# compressor.net
KiCad netlist of a schematic drawn in EAGLE
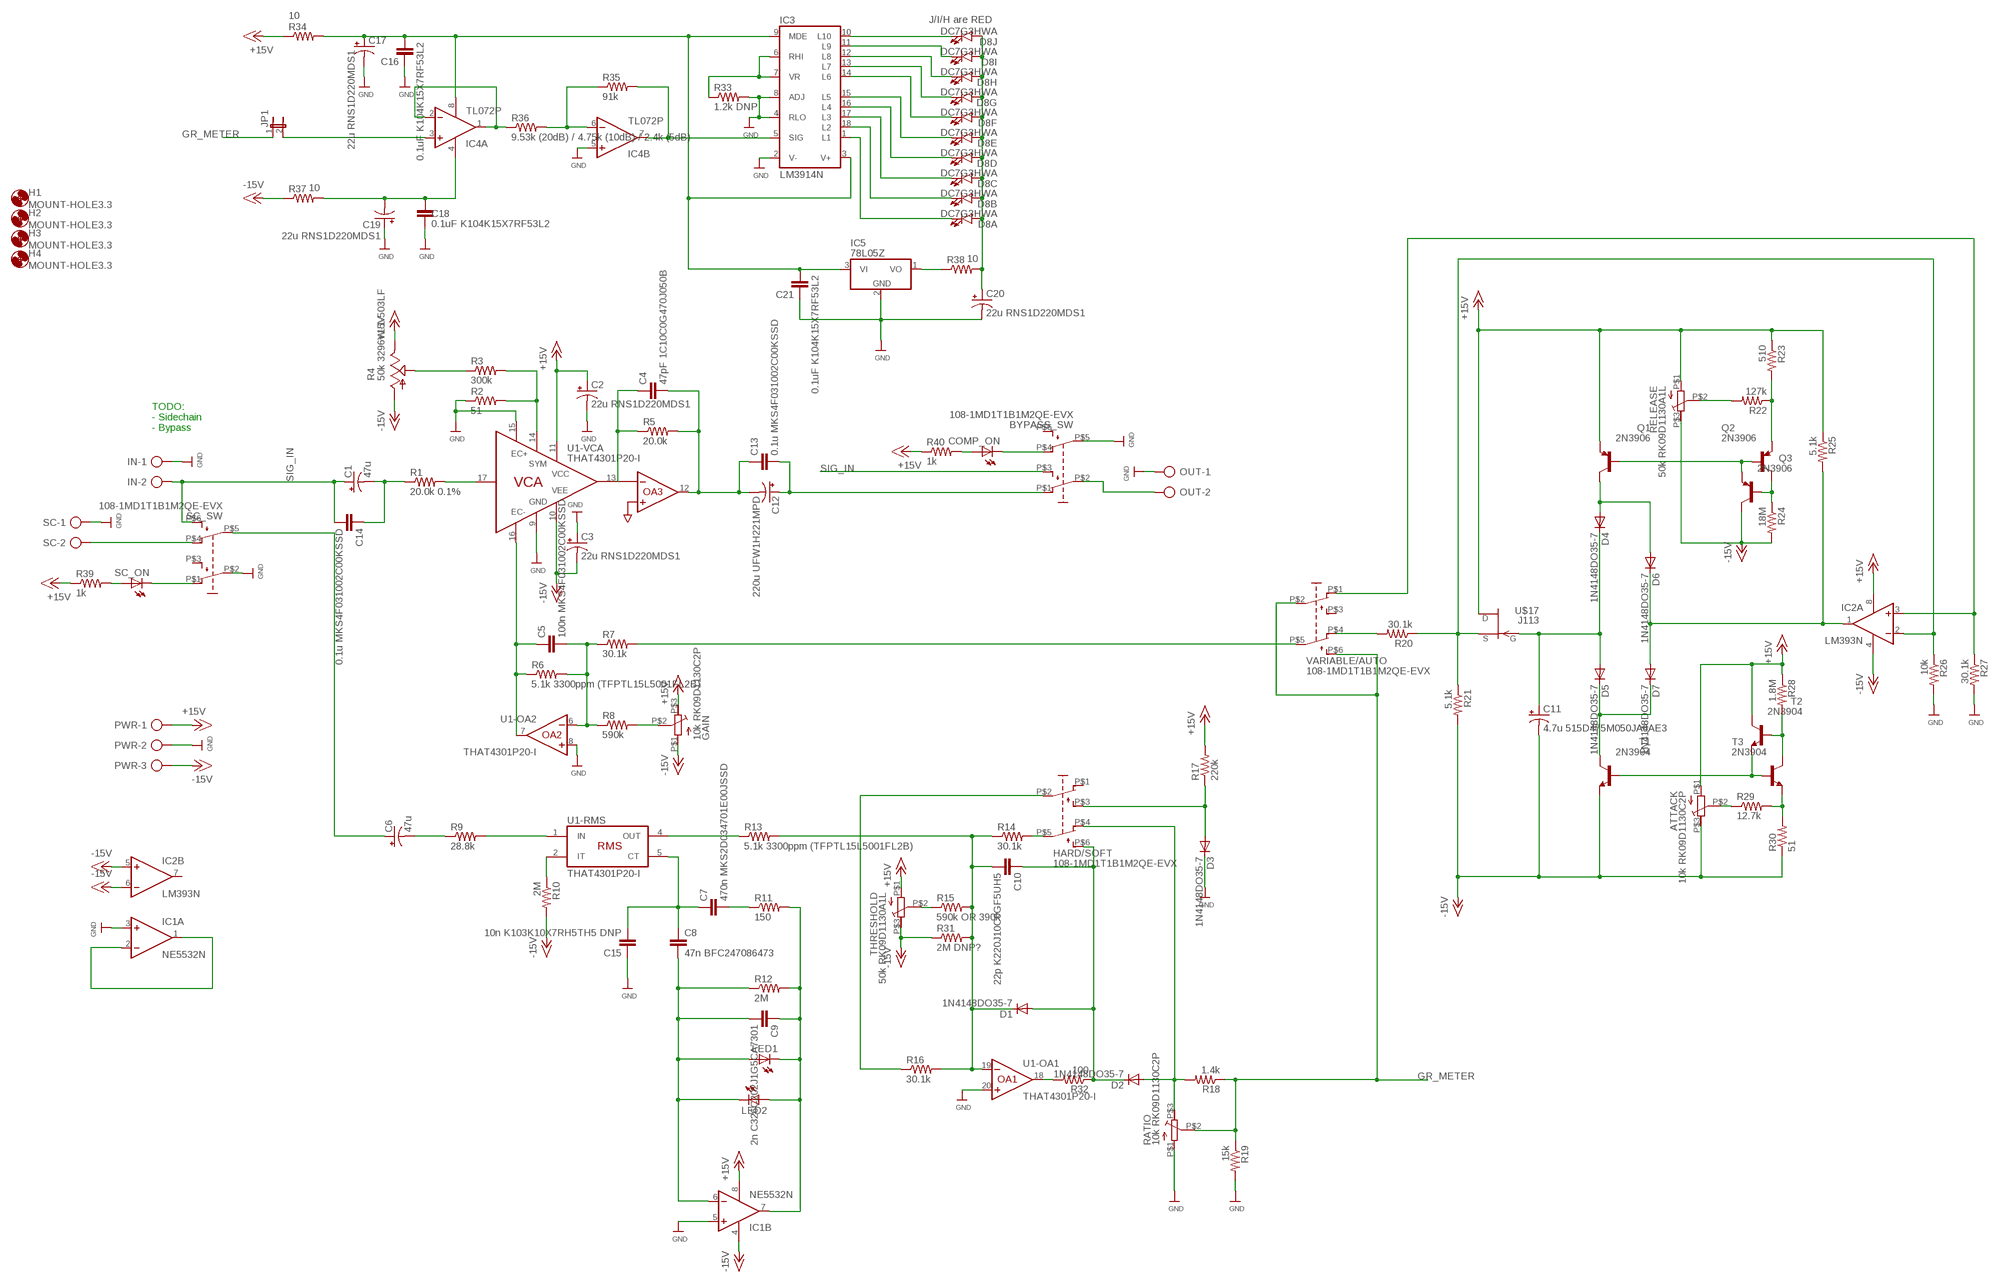
[diagram p0: schematic, sheet 1]

(export (version "E")
  (design (tool "Eeschema 10.0.6"))
  (components
    (comp (ref "ATTACK")
      (value "10k RK09D1130C2P")
      (footprint "eagle-import:ALPS-RK09D1130")
      (libsource (lib "eagle-import") (part "ALPS-RK09D"))
    )
    (comp (ref "BYPASS_SW")
      (value "108-1MD1T1B1M2QE-EVX")
      (footprint "eagle-import:108-1MD1T1B1M2QE-EVX")
      (libsource (lib "eagle-import") (part "108-1MD1T1B1M2QE-EVX"))
    )
    (comp (ref "C1")
      (value "47u")
      (footprint "eagle-import:B45181D")
      (libsource (lib "eagle-import") (part "CPOL-USB45181D"))
    )
    (comp (ref "C2")
      (value "22u RNS1D220MDS1")
      (footprint "eagle-import:E2,5-7")
      (libsource (lib "eagle-import") (part "CPOL-USE2.5-7"))
    )
    (comp (ref "C3")
      (value "22u RNS1D220MDS1")
      (footprint "eagle-import:E2,5-7")
      (libsource (lib "eagle-import") (part "CPOL-USE2.5-7"))
    )
    (comp (ref "C4")
      (value "47pF 1C10C0G470J050B")
      (footprint "eagle-import:C025-060X050")
      (libsource (lib "eagle-import") (part "C-EU025-060X050"))
    )
    (comp (ref "C5")
      (value "100n MKS4F031002C00KSSD")
      (footprint "eagle-import:C7.5B4")
      (libsource (lib "eagle-import") (part "C7.5/4"))
    )
    (comp (ref "C6")
      (value "47u")
      (footprint "eagle-import:B45181D")
      (fields (field (name "MPN") "ERJ-1TRQFR47U"))
      (libsource (lib "eagle-import") (part "CPOL-USB45181D"))
    )
    (comp (ref "C7")
      (value "470n MKS2D034701E00JSSD")
      (footprint "eagle-import:C5B4.5")
      (libsource (lib "eagle-import") (part "C5/4.5"))
    )
    (comp (ref "C8")
      (value "47n BFC247086473")
      (footprint "eagle-import:C5B7.2")
      (libsource (lib "eagle-import") (part "C5/7.2"))
    )
    (comp (ref "C9")
      (value "2n C326C202J1G5CA7301")
      (footprint "eagle-import:C5B2.5")
      (libsource (lib "eagle-import") (part "C5/2.5"))
    )
    (comp (ref "C10")
      (value "22p K220J10C0GF5UH5")
      (footprint "eagle-import:C050-035X075")
      (libsource (lib "eagle-import") (part "C-EU050-035X075"))
    )
    (comp (ref "C11")
      (value "4.7u 515D475M050JA6AE3")
      (footprint "eagle-import:E2-5")
      (libsource (lib "eagle-import") (part "CPOL-USE2-5"))
    )
    (comp (ref "C12")
      (value "220u UFW1H221MPD")
      (footprint "eagle-import:E5-10,5")
      (libsource (lib "eagle-import") (part "CPOL-USE5-10.5"))
    )
    (comp (ref "C13")
      (value "0.1u MKS4F031002C00KSSD")
      (footprint "eagle-import:C7.5B4")
      (libsource (lib "eagle-import") (part "C7.5/4"))
    )
    (comp (ref "C14")
      (value "0.1u MKS4F031002C00KSSD")
      (footprint "eagle-import:C7.5B4")
      (libsource (lib "eagle-import") (part "C7.5/4"))
    )
    (comp (ref "C15")
      (value "10n K103K10X7RH5TH5 DNP")
      (footprint "eagle-import:C050-025X075")
      (libsource (lib "eagle-import") (part "C-EU050-025X075"))
    )
    (comp (ref "C16")
      (value "0.1uF K104K15X7RF53L2")
      (footprint "eagle-import:C025-024X044")
      (libsource (lib "eagle-import") (part "C-EU025-024X044"))
    )
    (comp (ref "C17")
      (value "22u RNS1D220MDS1")
      (footprint "eagle-import:E2,5-7")
      (libsource (lib "eagle-import") (part "CPOL-USE2.5-7"))
    )
    (comp (ref "C18")
      (value "0.1uF K104K15X7RF53L2")
      (footprint "eagle-import:C025-024X044")
      (libsource (lib "eagle-import") (part "C-EU025-024X044"))
    )
    (comp (ref "C19")
      (value "22u RNS1D220MDS1")
      (footprint "eagle-import:E2,5-7")
      (libsource (lib "eagle-import") (part "CPOL-USE2.5-7"))
    )
    (comp (ref "C20")
      (value "22u RNS1D220MDS1")
      (footprint "eagle-import:E2,5-7")
      (libsource (lib "eagle-import") (part "CPOL-USE2.5-7"))
    )
    (comp (ref "C21")
      (value "0.1uF K104K15X7RF53L2")
      (footprint "eagle-import:C025-024X044")
      (libsource (lib "eagle-import") (part "C-EU025-024X044"))
    )
    (comp (ref "COMP_ON")
      (value "LED5MM")
      (footprint "eagle-import:LED5MM")
      (libsource (lib "eagle-import") (part "LED5MM"))
    )
    (comp (ref "D1")
      (value "1N4148DO35-7")
      (footprint "eagle-import:DO35-7")
      (libsource (lib "eagle-import") (part "1N4148DO35-7"))
    )
    (comp (ref "D2")
      (value "1N4148DO35-7")
      (footprint "eagle-import:DO35-7")
      (libsource (lib "eagle-import") (part "1N4148DO35-7"))
    )
    (comp (ref "D3")
      (value "1N4148DO35-7")
      (footprint "eagle-import:DO35-7")
      (libsource (lib "eagle-import") (part "1N4148DO35-7"))
    )
    (comp (ref "D4")
      (value "1N4148DO35-7")
      (footprint "eagle-import:DO35-7")
      (libsource (lib "eagle-import") (part "1N4148DO35-7"))
    )
    (comp (ref "D5")
      (value "1N4148DO35-7")
      (footprint "eagle-import:DO35-7")
      (libsource (lib "eagle-import") (part "1N4148DO35-7"))
    )
    (comp (ref "D6")
      (value "1N4148DO35-7")
      (footprint "eagle-import:DO35-7")
      (libsource (lib "eagle-import") (part "1N4148DO35-7"))
    )
    (comp (ref "D7")
      (value "1N4148DO35-7")
      (footprint "eagle-import:DO35-7")
      (libsource (lib "eagle-import") (part "1N4148DO35-7"))
    )
    (comp (ref "D8")
      (value "DC7G3HWA")
      (footprint "eagle-import:LED_BARGAPH_10")
      (fields (field (name "OC_NEWARK") "unknown"))
      (libsource (lib "eagle-import") (part "LED_BARGRAPH_10"))
    )
    (comp (ref "GAIN")
      (value "10k RK09D1130C2P")
      (footprint "eagle-import:ALPS-RK09D1130")
      (libsource (lib "eagle-import") (part "ALPS-RK09D"))
    )
    (comp (ref "H1")
      (value "MOUNT-HOLE3.3")
      (footprint "eagle-import:3,3")
      (libsource (lib "eagle-import") (part "MOUNT-HOLE3.3"))
    )
    (comp (ref "H2")
      (value "MOUNT-HOLE3.3")
      (footprint "eagle-import:3,3")
      (libsource (lib "eagle-import") (part "MOUNT-HOLE3.3"))
    )
    (comp (ref "H3")
      (value "MOUNT-HOLE3.3")
      (footprint "eagle-import:3,3")
      (libsource (lib "eagle-import") (part "MOUNT-HOLE3.3"))
    )
    (comp (ref "H4")
      (value "MOUNT-HOLE3.3")
      (footprint "eagle-import:3,3")
      (libsource (lib "eagle-import") (part "MOUNT-HOLE3.3"))
    )
    (comp (ref "HARD/SOFT")
      (value "108-1MD1T1B1M2QE-EVX")
      (footprint "eagle-import:108-1MD1T1B1M2QE-EVX")
      (libsource (lib "eagle-import") (part "108-1MD1T1B1M2QE-EVX"))
    )
    (comp (ref "IC1")
      (value "NE5532N")
      (footprint "eagle-import:DIL08")
      (fields (field (name "OC_NEWARK") "unknown"))
      (libsource (lib "eagle-import") (part "NE5532N"))
    )
    (comp (ref "IC2")
      (value "LM393N")
      (footprint "eagle-import:DIL08")
      (fields (field (name "OC_NEWARK") "unknown"))
      (libsource (lib "eagle-import") (part "LM393N"))
    )
    (comp (ref "IC3")
      (value "LM3914N")
      (footprint "eagle-import:DIL18")
      (libsource (lib "eagle-import") (part "LM3914N"))
    )
    (comp (ref "IC4")
      (value "TL072P")
      (footprint "eagle-import:DIL08")
      (fields (field (name "OC_NEWARK") "unknown"))
      (libsource (lib "eagle-import") (part "TL072P"))
    )
    (comp (ref "IC5")
      (value "78L05Z")
      (footprint "eagle-import:TO92")
      (libsource (lib "eagle-import") (part "78ZL05"))
    )
    (comp (ref "IN")
      (value "AK500/2")
      (footprint "eagle-import:AK500_2")
      (libsource (lib "eagle-import") (part "AK500/2"))
    )
    (comp (ref "JP1")
      (value "JP1E")
      (footprint "eagle-import:JP1")
      (libsource (lib "eagle-import") (part "JP1E"))
    )
    (comp (ref "LED1")
      (value "LED5MM")
      (footprint "eagle-import:LED5MM")
      (libsource (lib "eagle-import") (part "LED5MM"))
    )
    (comp (ref "LED2")
      (value "LED5MM")
      (footprint "eagle-import:LED5MM")
      (libsource (lib "eagle-import") (part "LED5MM"))
    )
    (comp (ref "OUT")
      (value "AK500/2")
      (footprint "eagle-import:AK500_2")
      (libsource (lib "eagle-import") (part "AK500/2"))
    )
    (comp (ref "PWR")
      (value "AK500/3")
      (footprint "eagle-import:AK500_3")
      (libsource (lib "eagle-import") (part "AK500/3"))
    )
    (comp (ref "Q1")
      (value "2N3906")
      (footprint "eagle-import:TO92")
      (libsource (lib "eagle-import") (part "2N3906"))
    )
    (comp (ref "Q2")
      (value "2N3906")
      (footprint "eagle-import:TO92")
      (libsource (lib "eagle-import") (part "2N3906"))
    )
    (comp (ref "Q3")
      (value "2N3906")
      (footprint "eagle-import:TO92")
      (libsource (lib "eagle-import") (part "2N3906"))
    )
    (comp (ref "R1")
      (value "20.0k 0.1%")
      (footprint "eagle-import:0204_7")
      (libsource (lib "eagle-import") (part "R-US_0204/7"))
    )
    (comp (ref "R2")
      (value "51")
      (footprint "eagle-import:0204_7")
      (libsource (lib "eagle-import") (part "R-US_0204/7"))
    )
    (comp (ref "R3")
      (value "300k")
      (footprint "eagle-import:0204_7")
      (libsource (lib "eagle-import") (part "R-US_0204/7"))
    )
    (comp (ref "R4")
      (value "50k 3296W-1-503LF")
      (footprint "eagle-import:S64W")
      (libsource (lib "eagle-import") (part "TRIM_US-S64W"))
    )
    (comp (ref "R5")
      (value "20.0k")
      (footprint "eagle-import:0204_7")
      (libsource (lib "eagle-import") (part "R-US_0204/7"))
    )
    (comp (ref "R6")
      (value "5.1k 3300ppm (TFPTL15L5001FL2B)")
      (footprint "eagle-import:0204_7")
      (libsource (lib "eagle-import") (part "R-US_0204/7"))
    )
    (comp (ref "R7")
      (value "30.1k")
      (footprint "eagle-import:0204_7")
      (libsource (lib "eagle-import") (part "R-US_0204/7"))
    )
    (comp (ref "R8")
      (value "590k")
      (footprint "eagle-import:0204_7")
      (libsource (lib "eagle-import") (part "R-US_0204/7"))
    )
    (comp (ref "R9")
      (value "28.8k")
      (footprint "eagle-import:0204_7")
      (libsource (lib "eagle-import") (part "R-US_0204/7"))
    )
    (comp (ref "R10")
      (value "2M")
      (footprint "eagle-import:0204_7")
      (libsource (lib "eagle-import") (part "R-US_0204/7"))
    )
    (comp (ref "R11")
      (value "150")
      (footprint "eagle-import:0204_7")
      (libsource (lib "eagle-import") (part "R-US_0204/7"))
    )
    (comp (ref "R12")
      (value "2M")
      (footprint "eagle-import:0204_7")
      (libsource (lib "eagle-import") (part "R-US_0204/7"))
    )
    (comp (ref "R13")
      (value "5.1k 3300ppm (TFPTL15L5001FL2B)")
      (footprint "eagle-import:0204_7")
      (libsource (lib "eagle-import") (part "R-US_0204/7"))
    )
    (comp (ref "R14")
      (value "30.1k")
      (footprint "eagle-import:0204_7")
      (libsource (lib "eagle-import") (part "R-US_0204/7"))
    )
    (comp (ref "R15")
      (value "590k OR 390k")
      (footprint "eagle-import:0204_7")
      (libsource (lib "eagle-import") (part "R-US_0204/7"))
    )
    (comp (ref "R16")
      (value "30.1k")
      (footprint "eagle-import:0204_7")
      (libsource (lib "eagle-import") (part "R-US_0204/7"))
    )
    (comp (ref "R17")
      (value "220k")
      (footprint "eagle-import:0204_7")
      (libsource (lib "eagle-import") (part "R-US_0204/7"))
    )
    (comp (ref "R18")
      (value "1.4k")
      (footprint "eagle-import:0204_7")
      (libsource (lib "eagle-import") (part "R-US_0204/7"))
    )
    (comp (ref "R19")
      (value "15k")
      (footprint "eagle-import:0204_7")
      (libsource (lib "eagle-import") (part "R-US_0204/7"))
    )
    (comp (ref "R20")
      (value "30.1k")
      (footprint "eagle-import:0204_7")
      (libsource (lib "eagle-import") (part "R-US_0204/7"))
    )
    (comp (ref "R21")
      (value "5.1k")
      (footprint "eagle-import:0204_7")
      (libsource (lib "eagle-import") (part "R-US_0204/7"))
    )
    (comp (ref "R22")
      (value "127k")
      (footprint "eagle-import:0204_7")
      (libsource (lib "eagle-import") (part "R-US_0204/7"))
    )
    (comp (ref "R23")
      (value "510")
      (footprint "eagle-import:0204_7")
      (libsource (lib "eagle-import") (part "R-US_0204/7"))
    )
    (comp (ref "R24")
      (value "18M")
      (footprint "eagle-import:0204_7")
      (libsource (lib "eagle-import") (part "R-US_0204/7"))
    )
    (comp (ref "R25")
      (value "5.1k")
      (footprint "eagle-import:0204_7")
      (libsource (lib "eagle-import") (part "R-US_0204/7"))
    )
    (comp (ref "R26")
      (value "10k")
      (footprint "eagle-import:0204_7")
      (libsource (lib "eagle-import") (part "R-US_0204/7"))
    )
    (comp (ref "R27")
      (value "30.1k")
      (footprint "eagle-import:0204_7")
      (libsource (lib "eagle-import") (part "R-US_0204/7"))
    )
    (comp (ref "R28")
      (value "1.8M")
      (footprint "eagle-import:0204_7")
      (libsource (lib "eagle-import") (part "R-US_0204/7"))
    )
    (comp (ref "R29")
      (value "12.7k")
      (footprint "eagle-import:0204_7")
      (libsource (lib "eagle-import") (part "R-US_0204/7"))
    )
    (comp (ref "R30")
      (value "51")
      (footprint "eagle-import:0204_7")
      (libsource (lib "eagle-import") (part "R-US_0204/7"))
    )
    (comp (ref "R31")
      (value "2M DNP?")
      (footprint "eagle-import:0204_7")
      (libsource (lib "eagle-import") (part "R-US_0204/7"))
    )
    (comp (ref "R32")
      (value "100")
      (footprint "eagle-import:0204_7")
      (libsource (lib "eagle-import") (part "R-US_0204/7"))
    )
    (comp (ref "R33")
      (value "1.2k DNP")
      (footprint "eagle-import:0204_7")
      (libsource (lib "eagle-import") (part "R-US_0204/7"))
    )
    (comp (ref "R34")
      (value "10")
      (footprint "eagle-import:0204_7")
      (libsource (lib "eagle-import") (part "R-US_0204/7"))
    )
    (comp (ref "R35")
      (value "91k")
      (footprint "eagle-import:0204_7")
      (libsource (lib "eagle-import") (part "R-US_0204/7"))
    )
    (comp (ref "R36")
      (value "9.53k (20dB) / 4.75k (10dB) / 2.4k (5dB)")
      (footprint "eagle-import:0204_7")
      (libsource (lib "eagle-import") (part "R-US_0204/7"))
    )
    (comp (ref "R37")
      (value "10")
      (footprint "eagle-import:0204_7")
      (libsource (lib "eagle-import") (part "R-US_0204/7"))
    )
    (comp (ref "R38")
      (value "10")
      (footprint "eagle-import:0204_7")
      (libsource (lib "eagle-import") (part "R-US_0204/7"))
    )
    (comp (ref "R39")
      (value "1k")
      (footprint "eagle-import:0204_7")
      (libsource (lib "eagle-import") (part "R-US_0204/7"))
    )
    (comp (ref "R40")
      (value "1k")
      (footprint "eagle-import:0204_7")
      (libsource (lib "eagle-import") (part "R-US_0204/7"))
    )
    (comp (ref "RATIO")
      (value "10k RK09D1130C2P")
      (footprint "eagle-import:ALPS-RK09D1130")
      (libsource (lib "eagle-import") (part "ALPS-RK09D"))
    )
    (comp (ref "RELEASE")
      (value "50k RK09D1130A1L")
      (footprint "eagle-import:ALPS-RK09D1130")
      (libsource (lib "eagle-import") (part "ALPS-RK09D"))
    )
    (comp (ref "SC")
      (value "AK500/2")
      (footprint "eagle-import:AK500_2")
      (libsource (lib "eagle-import") (part "AK500/2"))
    )
    (comp (ref "SC_ON")
      (value "LED5MM")
      (footprint "eagle-import:LED5MM")
      (libsource (lib "eagle-import") (part "LED5MM"))
    )
    (comp (ref "SC_SW")
      (value "108-1MD1T1B1M2QE-EVX")
      (footprint "eagle-import:108-1MD1T1B1M2QE-EVX")
      (libsource (lib "eagle-import") (part "108-1MD1T1B1M2QE-EVX"))
    )
    (comp (ref "T1")
      (value "2N3904")
      (footprint "eagle-import:TO92")
      (libsource (lib "eagle-import") (part "2N3904"))
    )
    (comp (ref "T2")
      (value "2N3904")
      (footprint "eagle-import:TO92")
      (libsource (lib "eagle-import") (part "2N3904"))
    )
    (comp (ref "T3")
      (value "2N3904")
      (footprint "eagle-import:TO92")
      (libsource (lib "eagle-import") (part "2N3904"))
    )
    (comp (ref "THRESHOLD")
      (value "50k RK09D1130A1L")
      (footprint "eagle-import:ALPS-RK09D1130")
      (libsource (lib "eagle-import") (part "ALPS-RK09D"))
    )
    (comp (ref "U$17")
      (value "J113")
      (footprint "eagle-import:J113-TO92")
      (libsource (lib "eagle-import") (part "J113"))
    )
    (comp (ref "U1")
      (value "THAT4301P20-I")
      (footprint "eagle-import:DIL20")
      (fields (field (name "OC_NEWARK") "unknown"))
      (libsource (lib "eagle-import") (part "THAT4301P20-I"))
    )
    (comp (ref "VARIABLE/AUTO")
      (value "108-1MD1T1B1M2QE-EVX")
      (footprint "eagle-import:108-1MD1T1B1M2QE-EVX")
      (libsource (lib "eagle-import") (part "108-1MD1T1B1M2QE-EVX"))
    )
  )
  (nets
    (net (code "1") (name "+15V") (class "Default")
      (node (ref "ATTACK") (pin "P$1") (pinfunction "E_P$1") (pintype "passive"))
      (node (ref "C2") (pin "+") (pinfunction "+_+") (pintype "passive"))
      (node (ref "GAIN") (pin "P$3") (pinfunction "A_P$3") (pintype "passive"))
      (node (ref "IC1") (pin "8") (pinfunction "V+_8") (pintype "power_in"))
      (node (ref "IC2") (pin "8") (pinfunction "V+_8") (pintype "power_in"))
      (node (ref "PWR") (pin "1") (pinfunction "KL_1") (pintype "passive"))
      (node (ref "Q1") (pin "3") (pinfunction "E_3") (pintype "passive"))
      (node (ref "R17") (pin "2") (pinfunction "2_2") (pintype "passive"))
      (node (ref "R23") (pin "1") (pinfunction "1_1") (pintype "passive"))
      (node (ref "R25") (pin "1") (pinfunction "1_1") (pintype "passive"))
      (node (ref "R28") (pin "1") (pinfunction "1_1") (pintype "passive"))
      (node (ref "R34") (pin "1") (pinfunction "1_1") (pintype "passive"))
      (node (ref "R39") (pin "1") (pinfunction "1_1") (pintype "passive"))
      (node (ref "R4") (pin "E") (pinfunction "E_E") (pintype "passive"))
      (node (ref "R40") (pin "1") (pinfunction "1_1") (pintype "passive"))
      (node (ref "RELEASE") (pin "P$1") (pinfunction "E_P$1") (pintype "passive"))
      (node (ref "T2") (pin "1") (pinfunction "C_1") (pintype "passive"))
      (node (ref "THRESHOLD") (pin "P$1") (pinfunction "E_P$1") (pintype "passive"))
      (node (ref "U$17") (pin "D") (pinfunction "D_D") (pintype "passive"))
      (node (ref "U1") (pin "11") (pinfunction "VCC_11") (pintype "power_in"))
    )
    (net (code "2") (name "-15V") (class "Default")
      (node (ref "ATTACK") (pin "P$3") (pinfunction "A_P$3") (pintype "passive"))
      (node (ref "C11") (pin "-") (pinfunction "-_-") (pintype "passive"))
      (node (ref "C3") (pin "-") (pinfunction "-_-") (pintype "passive"))
      (node (ref "GAIN") (pin "P$1") (pinfunction "E_P$1") (pintype "passive"))
      (node (ref "IC1") (pin "4") (pinfunction "V-_4") (pintype "power_in"))
      (node (ref "IC2") (pin "4") (pinfunction "V-_4") (pintype "power_in"))
      (node (ref "IC2") (pin "5") (pinfunction "+IN_5") (pintype "input"))
      (node (ref "IC2") (pin "6") (pinfunction "-IN_6") (pintype "input"))
      (node (ref "PWR") (pin "3") (pinfunction "KL_3") (pintype "passive"))
      (node (ref "Q3") (pin "1") (pinfunction "C_1") (pintype "passive"))
      (node (ref "R10") (pin "2") (pinfunction "2_2") (pintype "passive"))
      (node (ref "R21") (pin "2") (pinfunction "2_2") (pintype "passive"))
      (node (ref "R24") (pin "2") (pinfunction "2_2") (pintype "passive"))
      (node (ref "R30") (pin "1") (pinfunction "1_1") (pintype "passive"))
      (node (ref "R31") (pin "1") (pinfunction "1_1") (pintype "passive"))
      (node (ref "R37") (pin "1") (pinfunction "1_1") (pintype "passive"))
      (node (ref "R4") (pin "A") (pinfunction "A_A") (pintype "passive"))
      (node (ref "RELEASE") (pin "P$3") (pinfunction "A_P$3") (pintype "passive"))
      (node (ref "T1") (pin "3") (pinfunction "E_3") (pintype "passive"))
      (node (ref "THRESHOLD") (pin "P$3") (pinfunction "A_P$3") (pintype "passive"))
      (node (ref "U1") (pin "10") (pinfunction "VEE_10") (pintype "power_in"))
    )
    (net (code "3") (name "/GR_METER") (class "Default")
      (node (ref "JP1") (pin "1") (pinfunction "1_1") (pintype "passive"))
      (node (ref "R18") (pin "1") (pinfunction "1_1") (pintype "passive"))
      (node (ref "R19") (pin "1") (pinfunction "1_1") (pintype "passive"))
      (node (ref "RATIO") (pin "P$2") (pinfunction "S_P$2") (pintype "passive"))
      (node (ref "VARIABLE/AUTO") (pin "P$2") (pinfunction "P_P$2") (pintype "passive"))
      (node (ref "VARIABLE/AUTO") (pin "P$6") (pinfunction "S1_P$6") (pintype "passive"))
    )
    (net (code "4") (name "/SIG_IN") (class "Default")
      (node (ref "BYPASS_SW") (pin "P$3") (pinfunction "S_P$3") (pintype "passive"))
      (node (ref "C1") (pin "+") (pinfunction "+_+") (pintype "passive"))
      (node (ref "C14") (pin "2") (pinfunction "2_2") (pintype "passive"))
      (node (ref "IN") (pin "2") (pinfunction "KL_2") (pintype "passive"))
      (node (ref "SC_SW") (pin "P$6") (pinfunction "S1_P$6") (pintype "passive"))
    )
    (net (code "5") (name "GND") (class "Default")
      (node (ref "BYPASS_SW") (pin "P$5") (pinfunction "P1_P$5") (pintype "passive"))
      (node (ref "C15") (pin "1") (pinfunction "1_1") (pintype "passive"))
      (node (ref "C16") (pin "1") (pinfunction "1_1") (pintype "passive"))
      (node (ref "C17") (pin "-") (pinfunction "-_-") (pintype "passive"))
      (node (ref "C18") (pin "1") (pinfunction "1_1") (pintype "passive"))
      (node (ref "C19") (pin "+") (pinfunction "+_+") (pintype "passive"))
      (node (ref "C2") (pin "-") (pinfunction "-_-") (pintype "passive"))
      (node (ref "C20") (pin "-") (pinfunction "-_-") (pintype "passive"))
      (node (ref "C21") (pin "1") (pinfunction "1_1") (pintype "passive"))
      (node (ref "C3") (pin "+") (pinfunction "+_+") (pintype "passive"))
      (node (ref "D3") (pin "C") (pinfunction "C_C") (pintype "passive"))
      (node (ref "IC1") (pin "3") (pinfunction "+IN_3") (pintype "input"))
      (node (ref "IC1") (pin "5") (pinfunction "+IN_5") (pintype "input"))
      (node (ref "IC3") (pin "2") (pinfunction "V-_2") (pintype "power_in"))
      (node (ref "IC3") (pin "4") (pinfunction "RLO_4") (pintype "input"))
      (node (ref "IC3") (pin "8") (pinfunction "ADJ_8") (pintype "input"))
      (node (ref "IC4") (pin "5") (pinfunction "+IN_5") (pintype "input"))
      (node (ref "IC5") (pin "2") (pinfunction "GND_2") (pintype "passive"))
      (node (ref "IN") (pin "1") (pinfunction "KL_1") (pintype "passive"))
      (node (ref "OUT") (pin "1") (pinfunction "KL_1") (pintype "passive"))
      (node (ref "PWR") (pin "2") (pinfunction "KL_2") (pintype "passive"))
      (node (ref "R19") (pin "2") (pinfunction "2_2") (pintype "passive"))
      (node (ref "R2") (pin "1") (pinfunction "1_1") (pintype "passive"))
      (node (ref "R26") (pin "2") (pinfunction "2_2") (pintype "passive"))
      (node (ref "R27") (pin "2") (pinfunction "2_2") (pintype "passive"))
      (node (ref "R33") (pin "2") (pinfunction "2_2") (pintype "passive"))
      (node (ref "RATIO") (pin "P$1") (pinfunction "E_P$1") (pintype "passive"))
      (node (ref "SC") (pin "1") (pinfunction "KL_1") (pintype "passive"))
      (node (ref "SC_SW") (pin "P$2") (pinfunction "P_P$2") (pintype "passive"))
      (node (ref "U1") (pin "15") (pinfunction "EC+_15") (pintype "passive"))
      (node (ref "U1") (pin "20") (pinfunction "+IN_20") (pintype "input"))
      (node (ref "U1") (pin "8") (pinfunction "+IN_8") (pintype "input"))
      (node (ref "U1") (pin "9") (pinfunction "GND_9") (pintype "power_in"))
    )
    (net (code "6") (name "Net-(ATTACK-S)") (class "Default")
      (node (ref "ATTACK") (pin "P$2") (pinfunction "S_P$2") (pintype "passive"))
      (node (ref "R29") (pin "1") (pinfunction "1_1") (pintype "passive"))
    )
    (net (code "7") (name "Net-(BYPASS_SW-O)") (class "Default")
      (node (ref "BYPASS_SW") (pin "P$1") (pinfunction "O_P$1") (pintype "passive"))
      (node (ref "C12") (pin "+") (pinfunction "+_+") (pintype "passive"))
      (node (ref "C13") (pin "2") (pinfunction "2_2") (pintype "passive"))
    )
    (net (code "8") (name "Net-(BYPASS_SW-O1)") (class "Default")
      (node (ref "BYPASS_SW") (pin "P$4") (pinfunction "O1_P$4") (pintype "passive"))
      (node (ref "COMP_ON") (pin "K") (pinfunction "C_K") (pintype "passive"))
    )
    (net (code "9") (name "Net-(BYPASS_SW-P)") (class "Default")
      (node (ref "BYPASS_SW") (pin "P$2") (pinfunction "P_P$2") (pintype "passive"))
      (node (ref "OUT") (pin "2") (pinfunction "KL_2") (pintype "passive"))
    )
    (net (code "10") (name "Net-(C1-Pad-)") (class "Default")
      (node (ref "C1") (pin "-") (pinfunction "-_-") (pintype "passive"))
      (node (ref "C14") (pin "1") (pinfunction "1_1") (pintype "passive"))
      (node (ref "R1") (pin "1") (pinfunction "1_1") (pintype "passive"))
    )
    (net (code "11") (name "Net-(C6-Pad-)") (class "Default")
      (node (ref "C6") (pin "-") (pinfunction "-_-") (pintype "passive"))
      (node (ref "R9") (pin "1") (pinfunction "1_1") (pintype "passive"))
    )
    (net (code "12") (name "Net-(C7-Pad2)") (class "Default")
      (node (ref "C7") (pin "2") (pinfunction "2_2") (pintype "passive"))
      (node (ref "R11") (pin "1") (pinfunction "1_1") (pintype "passive"))
    )
    (net (code "13") (name "Net-(C11-Pad+)") (class "Default")
      (node (ref "C11") (pin "+") (pinfunction "+_+") (pintype "passive"))
      (node (ref "D4") (pin "C") (pinfunction "C_C") (pintype "passive"))
      (node (ref "D5") (pin "A") (pinfunction "A_A") (pintype "passive"))
      (node (ref "U$17") (pin "G") (pinfunction "G_G") (pintype "passive"))
    )
    (net (code "14") (name "Net-(COMP_ON-PadA)") (class "Default")
      (node (ref "COMP_ON") (pin "A") (pinfunction "A_A") (pintype "passive"))
      (node (ref "R40") (pin "2") (pinfunction "2_2") (pintype "passive"))
    )
    (net (code "15") (name "Net-(D8A-A)") (class "Default")
      (node (ref "C20") (pin "+") (pinfunction "+_+") (pintype "passive"))
      (node (ref "D8") (pin "1") (pinfunction "A_1") (pintype "passive"))
      (node (ref "D8") (pin "10") (pinfunction "A_10") (pintype "passive"))
      (node (ref "D8") (pin "2") (pinfunction "A_2") (pintype "passive"))
      (node (ref "D8") (pin "3") (pinfunction "A_3") (pintype "passive"))
      (node (ref "D8") (pin "4") (pinfunction "A_4") (pintype "passive"))
      (node (ref "D8") (pin "5") (pinfunction "A_5") (pintype "passive"))
      (node (ref "D8") (pin "6") (pinfunction "A_6") (pintype "passive"))
      (node (ref "D8") (pin "7") (pinfunction "A_7") (pintype "passive"))
      (node (ref "D8") (pin "8") (pinfunction "A_8") (pintype "passive"))
      (node (ref "D8") (pin "9") (pinfunction "A_9") (pintype "passive"))
      (node (ref "R38") (pin "2") (pinfunction "2_2") (pintype "passive"))
    )
    (net (code "16") (name "Net-(D8A-C)") (class "Default")
      (node (ref "D8") (pin "20") (pinfunction "C_20") (pintype "passive"))
      (node (ref "IC3") (pin "1") (pinfunction "L1_1") (pintype "output"))
    )
    (net (code "17") (name "Net-(D8B-C)") (class "Default")
      (node (ref "D8") (pin "19") (pinfunction "C_19") (pintype "passive"))
      (node (ref "IC3") (pin "18") (pinfunction "L2_18") (pintype "output"))
    )
    (net (code "18") (name "Net-(D8C-C)") (class "Default")
      (node (ref "D8") (pin "18") (pinfunction "C_18") (pintype "passive"))
      (node (ref "IC3") (pin "17") (pinfunction "L3_17") (pintype "output"))
    )
    (net (code "19") (name "Net-(D8D-C)") (class "Default")
      (node (ref "D8") (pin "17") (pinfunction "C_17") (pintype "passive"))
      (node (ref "IC3") (pin "16") (pinfunction "L4_16") (pintype "output"))
    )
    (net (code "20") (name "Net-(D8E-C)") (class "Default")
      (node (ref "D8") (pin "16") (pinfunction "C_16") (pintype "passive"))
      (node (ref "IC3") (pin "15") (pinfunction "L5_15") (pintype "output"))
    )
    (net (code "21") (name "Net-(D8F-C)") (class "Default")
      (node (ref "D8") (pin "15") (pinfunction "C_15") (pintype "passive"))
      (node (ref "IC3") (pin "14") (pinfunction "L6_14") (pintype "output"))
    )
    (net (code "22") (name "Net-(D8G-C)") (class "Default")
      (node (ref "D8") (pin "14") (pinfunction "C_14") (pintype "passive"))
      (node (ref "IC3") (pin "13") (pinfunction "L7_13") (pintype "output"))
    )
    (net (code "23") (name "Net-(D8H-C)") (class "Default")
      (node (ref "D8") (pin "13") (pinfunction "C_13") (pintype "passive"))
      (node (ref "IC3") (pin "12") (pinfunction "L8_12") (pintype "output"))
    )
    (net (code "24") (name "Net-(D8I-C)") (class "Default")
      (node (ref "D8") (pin "12") (pinfunction "C_12") (pintype "passive"))
      (node (ref "IC3") (pin "11") (pinfunction "L9_11") (pintype "output"))
    )
    (net (code "25") (name "Net-(D8J-C)") (class "Default")
      (node (ref "D8") (pin "11") (pinfunction "C_11") (pintype "passive"))
      (node (ref "IC3") (pin "10") (pinfunction "L10_10") (pintype "output"))
    )
    (net (code "26") (name "Net-(GAIN-S)") (class "Default")
      (node (ref "GAIN") (pin "P$2") (pinfunction "S_P$2") (pintype "passive"))
      (node (ref "R8") (pin "2") (pinfunction "2_2") (pintype "passive"))
    )
    (net (code "27") (name "Net-(HARD/SOFT-O1)") (class "Default")
      (node (ref "D2") (pin "A") (pinfunction "A_A") (pintype "passive"))
      (node (ref "HARD/SOFT") (pin "P$4") (pinfunction "O1_P$4") (pintype "passive"))
      (node (ref "R18") (pin "2") (pinfunction "2_2") (pintype "passive"))
      (node (ref "RATIO") (pin "P$3") (pinfunction "A_P$3") (pintype "passive"))
    )
    (net (code "28") (name "Net-(HARD/SOFT-P)") (class "Default")
      (node (ref "HARD/SOFT") (pin "P$2") (pinfunction "P_P$2") (pintype "passive"))
      (node (ref "R16") (pin "1") (pinfunction "1_1") (pintype "passive"))
    )
    (net (code "29") (name "Net-(HARD/SOFT-P1)") (class "Default")
      (node (ref "HARD/SOFT") (pin "P$5") (pinfunction "P1_P$5") (pintype "passive"))
      (node (ref "R14") (pin "2") (pinfunction "2_2") (pintype "passive"))
    )
    (net (code "30") (name "Net-(HARD/SOFT-S)") (class "Default")
      (node (ref "D3") (pin "A") (pinfunction "A_A") (pintype "passive"))
      (node (ref "HARD/SOFT") (pin "P$3") (pinfunction "S_P$3") (pintype "passive"))
      (node (ref "R17") (pin "1") (pinfunction "1_1") (pintype "passive"))
    )
    (net (code "31") (name "Net-(HARD/SOFT-S1)") (class "Default")
      (node (ref "C10") (pin "1") (pinfunction "1_1") (pintype "passive"))
      (node (ref "D1") (pin "A") (pinfunction "A_A") (pintype "passive"))
      (node (ref "D2") (pin "C") (pinfunction "C_C") (pintype "passive"))
      (node (ref "HARD/SOFT") (pin "P$6") (pinfunction "S1_P$6") (pintype "passive"))
      (node (ref "R32") (pin "1") (pinfunction "1_1") (pintype "passive"))
    )
    (net (code "32") (name "Net-(IC1A--IN)") (class "Default")
      (node (ref "IC1") (pin "1") (pinfunction "OUT_1") (pintype "output"))
      (node (ref "IC1") (pin "2") (pinfunction "-IN_2") (pintype "input"))
    )
    (net (code "33") (name "Net-(IC1B--IN)") (class "Default")
      (node (ref "C8") (pin "2") (pinfunction "2_2") (pintype "passive"))
      (node (ref "C9") (pin "2") (pinfunction "2_2") (pintype "passive"))
      (node (ref "IC1") (pin "6") (pinfunction "-IN_6") (pintype "input"))
      (node (ref "LED1") (pin "A") (pinfunction "A_A") (pintype "passive"))
      (node (ref "LED2") (pin "K") (pinfunction "C_K") (pintype "passive"))
      (node (ref "R12") (pin "1") (pinfunction "1_1") (pintype "passive"))
    )
    (net (code "34") (name "Net-(IC1B-OUT)") (class "Default")
      (node (ref "C9") (pin "1") (pinfunction "1_1") (pintype "passive"))
      (node (ref "IC1") (pin "7") (pinfunction "OUT_7") (pintype "output"))
      (node (ref "LED1") (pin "K") (pinfunction "C_K") (pintype "passive"))
      (node (ref "LED2") (pin "A") (pinfunction "A_A") (pintype "passive"))
      (node (ref "R11") (pin "2") (pinfunction "2_2") (pintype "passive"))
      (node (ref "R12") (pin "2") (pinfunction "2_2") (pintype "passive"))
    )
    (net (code "35") (name "Net-(IC2A-+IN)") (class "Default")
      (node (ref "IC2") (pin "3") (pinfunction "+IN_3") (pintype "input"))
      (node (ref "R27") (pin "1") (pinfunction "1_1") (pintype "passive"))
      (node (ref "VARIABLE/AUTO") (pin "P$1") (pinfunction "O_P$1") (pintype "passive"))
    )
    (net (code "36") (name "Net-(IC2A--IN)") (class "Default")
      (node (ref "IC2") (pin "2") (pinfunction "-IN_2") (pintype "input"))
      (node (ref "R20") (pin "1") (pinfunction "1_1") (pintype "passive"))
      (node (ref "R21") (pin "1") (pinfunction "1_1") (pintype "passive"))
      (node (ref "R26") (pin "1") (pinfunction "1_1") (pintype "passive"))
      (node (ref "U$17") (pin "S") (pinfunction "S_S") (pintype "passive"))
    )
    (net (code "37") (name "Net-(IC2A-OUT)") (class "Default")
      (node (ref "D6") (pin "C") (pinfunction "C_C") (pintype "passive"))
      (node (ref "D7") (pin "A") (pinfunction "A_A") (pintype "passive"))
      (node (ref "IC2") (pin "1") (pinfunction "OUT_1") (pintype "output"))
      (node (ref "R25") (pin "2") (pinfunction "2_2") (pintype "passive"))
    )
    (net (code "38") (name "Net-(IC3-MDE)") (class "Default")
      (node (ref "C16") (pin "2") (pinfunction "2_2") (pintype "passive"))
      (node (ref "C17") (pin "+") (pinfunction "+_+") (pintype "passive"))
      (node (ref "C21") (pin "2") (pinfunction "2_2") (pintype "passive"))
      (node (ref "IC3") (pin "3") (pinfunction "V+_3") (pintype "power_in"))
      (node (ref "IC3") (pin "9") (pinfunction "MDE_9") (pintype "input"))
      (node (ref "IC4") (pin "8") (pinfunction "V+_8") (pintype "power_in"))
      (node (ref "IC5") (pin "3") (pinfunction "VI_3") (pintype "input"))
      (node (ref "R34") (pin "2") (pinfunction "2_2") (pintype "passive"))
    )
    (net (code "39") (name "Net-(IC3-RHI)") (class "Default")
      (node (ref "IC3") (pin "6") (pinfunction "RHI_6") (pintype "input"))
      (node (ref "IC3") (pin "7") (pinfunction "VR_7") (pintype "output"))
      (node (ref "R33") (pin "1") (pinfunction "1_1") (pintype "passive"))
    )
    (net (code "40") (name "Net-(IC3-SIG)") (class "Default")
      (node (ref "IC3") (pin "5") (pinfunction "SIG_5") (pintype "input"))
      (node (ref "IC4") (pin "7") (pinfunction "OUT_7") (pintype "output"))
      (node (ref "R35") (pin "2") (pinfunction "2_2") (pintype "passive"))
    )
    (net (code "41") (name "Net-(IC4A-+IN)") (class "Default")
      (node (ref "IC4") (pin "3") (pinfunction "+IN_3") (pintype "input"))
      (node (ref "JP1") (pin "2") (pinfunction "2_2") (pintype "passive"))
    )
    (net (code "42") (name "Net-(IC4A--IN)") (class "Default")
      (node (ref "IC4") (pin "1") (pinfunction "OUT_1") (pintype "output"))
      (node (ref "IC4") (pin "2") (pinfunction "-IN_2") (pintype "input"))
      (node (ref "R36") (pin "1") (pinfunction "1_1") (pintype "passive"))
    )
    (net (code "43") (name "Net-(IC4B--IN)") (class "Default")
      (node (ref "IC4") (pin "6") (pinfunction "-IN_6") (pintype "input"))
      (node (ref "R35") (pin "1") (pinfunction "1_1") (pintype "passive"))
      (node (ref "R36") (pin "2") (pinfunction "2_2") (pintype "passive"))
    )
    (net (code "44") (name "Net-(IC4C-V-)") (class "Default")
      (node (ref "C18") (pin "2") (pinfunction "2_2") (pintype "passive"))
      (node (ref "C19") (pin "-") (pinfunction "-_-") (pintype "passive"))
      (node (ref "IC4") (pin "4") (pinfunction "V-_4") (pintype "power_in"))
      (node (ref "R37") (pin "2") (pinfunction "2_2") (pintype "passive"))
    )
    (net (code "45") (name "Net-(IC5-VO)") (class "Default")
      (node (ref "IC5") (pin "1") (pinfunction "VO_1") (pintype "passive"))
      (node (ref "R38") (pin "1") (pinfunction "1_1") (pintype "passive"))
    )
    (net (code "46") (name "Net-(Q1-B)") (class "Default")
      (node (ref "Q1") (pin "2") (pinfunction "B_2") (pintype "passive"))
      (node (ref "Q2") (pin "2") (pinfunction "B_2") (pintype "passive"))
      (node (ref "Q3") (pin "3") (pinfunction "E_3") (pintype "passive"))
    )
    (net (code "47") (name "Net-(Q1-C)") (class "Default")
      (node (ref "D4") (pin "A") (pinfunction "A_A") (pintype "passive"))
      (node (ref "D6") (pin "A") (pinfunction "A_A") (pintype "passive"))
      (node (ref "Q1") (pin "1") (pinfunction "C_1") (pintype "passive"))
    )
    (net (code "48") (name "Net-(Q2-C)") (class "Default")
      (node (ref "Q2") (pin "1") (pinfunction "C_1") (pintype "passive"))
      (node (ref "Q3") (pin "2") (pinfunction "B_2") (pintype "passive"))
      (node (ref "R24") (pin "1") (pinfunction "1_1") (pintype "passive"))
    )
    (net (code "49") (name "Net-(Q2-E)") (class "Default")
      (node (ref "Q2") (pin "3") (pinfunction "E_3") (pintype "passive"))
      (node (ref "R22") (pin "1") (pinfunction "1_1") (pintype "passive"))
      (node (ref "R23") (pin "2") (pinfunction "2_2") (pintype "passive"))
    )
    (net (code "50") (name "Net-(R3-Pad1)") (class "Default")
      (node (ref "R3") (pin "1") (pinfunction "1_1") (pintype "passive"))
      (node (ref "R4") (pin "S") (pinfunction "S_S") (pintype "passive"))
    )
    (net (code "51") (name "Net-(R39-Pad2)") (class "Default")
      (node (ref "R39") (pin "2") (pinfunction "2_2") (pintype "passive"))
      (node (ref "SC_ON") (pin "A") (pinfunction "A_A") (pintype "passive"))
    )
    (net (code "52") (name "Net-(RELEASE-S)") (class "Default")
      (node (ref "R22") (pin "2") (pinfunction "2_2") (pintype "passive"))
      (node (ref "RELEASE") (pin "P$2") (pinfunction "S_P$2") (pintype "passive"))
    )
    (net (code "53") (name "Net-(SCB-KL)") (class "Default")
      (node (ref "SC") (pin "2") (pinfunction "KL_2") (pintype "passive"))
      (node (ref "SC_SW") (pin "P$4") (pinfunction "O1_P$4") (pintype "passive"))
    )
    (net (code "54") (name "Net-(SC_ON-C)") (class "Default")
      (node (ref "SC_ON") (pin "K") (pinfunction "C_K") (pintype "passive"))
      (node (ref "SC_SW") (pin "P$1") (pinfunction "O_P$1") (pintype "passive"))
    )
    (net (code "55") (name "Net-(SC_SW-P1)") (class "Default")
      (node (ref "C6") (pin "+") (pinfunction "+_+") (pintype "passive"))
      (node (ref "SC_SW") (pin "P$5") (pinfunction "P1_P$5") (pintype "passive"))
    )
    (net (code "56") (name "Net-(T1-B)") (class "Default")
      (node (ref "T1") (pin "2") (pinfunction "B_2") (pintype "passive"))
      (node (ref "T2") (pin "3") (pinfunction "E_3") (pintype "passive"))
      (node (ref "T3") (pin "2") (pinfunction "B_2") (pintype "passive"))
    )
    (net (code "57") (name "Net-(T1-C)") (class "Default")
      (node (ref "D5") (pin "C") (pinfunction "C_C") (pintype "passive"))
      (node (ref "D7") (pin "C") (pinfunction "C_C") (pintype "passive"))
      (node (ref "T1") (pin "1") (pinfunction "C_1") (pintype "passive"))
    )
    (net (code "58") (name "Net-(T2-B)") (class "Default")
      (node (ref "R28") (pin "2") (pinfunction "2_2") (pintype "passive"))
      (node (ref "T2") (pin "2") (pinfunction "B_2") (pintype "passive"))
      (node (ref "T3") (pin "1") (pinfunction "C_1") (pintype "passive"))
    )
    (net (code "59") (name "Net-(T3-E)") (class "Default")
      (node (ref "R29") (pin "2") (pinfunction "2_2") (pintype "passive"))
      (node (ref "R30") (pin "2") (pinfunction "2_2") (pintype "passive"))
      (node (ref "T3") (pin "3") (pinfunction "E_3") (pintype "passive"))
    )
    (net (code "60") (name "Net-(THRESHOLD-S)") (class "Default")
      (node (ref "R15") (pin "1") (pinfunction "1_1") (pintype "passive"))
      (node (ref "THRESHOLD") (pin "P$2") (pinfunction "S_P$2") (pintype "passive"))
    )
    (net (code "61") (name "Net-(U1A--IN)") (class "Default")
      (node (ref "C10") (pin "2") (pinfunction "2_2") (pintype "passive"))
      (node (ref "D1") (pin "C") (pinfunction "C_C") (pintype "passive"))
      (node (ref "R13") (pin "2") (pinfunction "2_2") (pintype "passive"))
      (node (ref "R14") (pin "1") (pinfunction "1_1") (pintype "passive"))
      (node (ref "R15") (pin "2") (pinfunction "2_2") (pintype "passive"))
      (node (ref "R16") (pin "2") (pinfunction "2_2") (pintype "passive"))
      (node (ref "R31") (pin "2") (pinfunction "2_2") (pintype "passive"))
      (node (ref "U1") (pin "19") (pinfunction "-IN_19") (pintype "input"))
    )
    (net (code "62") (name "Net-(U1A-OUT)") (class "Default")
      (node (ref "R32") (pin "2") (pinfunction "2_2") (pintype "passive"))
      (node (ref "U1") (pin "18") (pinfunction "OUT_18") (pintype "output"))
    )
    (net (code "63") (name "Net-(U1B--IN)") (class "Default")
      (node (ref "C5") (pin "2") (pinfunction "2_2") (pintype "passive"))
      (node (ref "R6") (pin "2") (pinfunction "2_2") (pintype "passive"))
      (node (ref "R7") (pin "1") (pinfunction "1_1") (pintype "passive"))
      (node (ref "R8") (pin "1") (pinfunction "1_1") (pintype "passive"))
      (node (ref "U1") (pin "6") (pinfunction "-IN_6") (pintype "input"))
    )
    (net (code "64") (name "Net-(U1B-OUT)") (class "Default")
      (node (ref "C5") (pin "1") (pinfunction "1_1") (pintype "passive"))
      (node (ref "R6") (pin "1") (pinfunction "1_1") (pintype "passive"))
      (node (ref "U1") (pin "16") (pinfunction "EC-_16") (pintype "passive"))
      (node (ref "U1") (pin "7") (pinfunction "OUT_7") (pintype "output"))
    )
    (net (code "65") (name "Net-(U1C-RMS-CT)") (class "Default")
      (node (ref "C15") (pin "2") (pinfunction "2_2") (pintype "passive"))
      (node (ref "C7") (pin "1") (pinfunction "1_1") (pintype "passive"))
      (node (ref "C8") (pin "1") (pinfunction "1_1") (pintype "passive"))
      (node (ref "U1") (pin "5") (pinfunction "RMS-CT_5") (pintype "passive"))
    )
    (net (code "66") (name "Net-(U1C-RMS-IN)") (class "Default")
      (node (ref "R9") (pin "2") (pinfunction "2_2") (pintype "passive"))
      (node (ref "U1") (pin "1") (pinfunction "RMS-IN_1") (pintype "input"))
    )
    (net (code "67") (name "Net-(U1C-RMS-IT)") (class "Default")
      (node (ref "R10") (pin "1") (pinfunction "1_1") (pintype "passive"))
      (node (ref "U1") (pin "2") (pinfunction "RMS-IT_2") (pintype "passive"))
    )
    (net (code "68") (name "Net-(U1C-RMS-OUT)") (class "Default")
      (node (ref "R13") (pin "1") (pinfunction "1_1") (pintype "passive"))
      (node (ref "U1") (pin "4") (pinfunction "RMS-OUT_4") (pintype "output"))
    )
    (net (code "69") (name "Net-(U1D-IN)") (class "Default")
      (node (ref "R1") (pin "2") (pinfunction "2_2") (pintype "passive"))
      (node (ref "U1") (pin "17") (pinfunction "IN_17") (pintype "input"))
    )
    (net (code "70") (name "Net-(U1D-OA3_OUT)") (class "Default")
      (node (ref "C12") (pin "-") (pinfunction "-_-") (pintype "passive"))
      (node (ref "C13") (pin "1") (pinfunction "1_1") (pintype "passive"))
      (node (ref "C4") (pin "2") (pinfunction "2_2") (pintype "passive"))
      (node (ref "R5") (pin "2") (pinfunction "2_2") (pintype "passive"))
      (node (ref "U1") (pin "12") (pinfunction "OA3_OUT_12") (pintype "output"))
    )
    (net (code "71") (name "Net-(U1D-SYM)") (class "Default")
      (node (ref "R2") (pin "2") (pinfunction "2_2") (pintype "passive"))
      (node (ref "R3") (pin "2") (pinfunction "2_2") (pintype "passive"))
      (node (ref "U1") (pin "14") (pinfunction "SYM_14") (pintype "passive"))
    )
    (net (code "72") (name "Net-(U1D-VCA_OUT)") (class "Default")
      (node (ref "C4") (pin "1") (pinfunction "1_1") (pintype "passive"))
      (node (ref "R5") (pin "1") (pinfunction "1_1") (pintype "passive"))
      (node (ref "U1") (pin "13") (pinfunction "VCA_OUT_13") (pintype "output"))
    )
    (net (code "73") (name "Net-(VARIABLE/AUTO-O1)") (class "Default")
      (node (ref "R20") (pin "2") (pinfunction "2_2") (pintype "passive"))
      (node (ref "VARIABLE/AUTO") (pin "P$4") (pinfunction "O1_P$4") (pintype "passive"))
    )
    (net (code "74") (name "Net-(VARIABLE/AUTO-P1)") (class "Default")
      (node (ref "R7") (pin "2") (pinfunction "2_2") (pintype "passive"))
      (node (ref "VARIABLE/AUTO") (pin "P$5") (pinfunction "P1_P$5") (pintype "passive"))
    )
    (net (code "75") (name "unconnected-(BYPASS_SW-S1-PadP$6)") (class "Default")
      (node (ref "BYPASS_SW") (pin "P$6") (pinfunction "S1_P$6") (pintype "passive"))
    )
    (net (code "76") (name "unconnected-(HARD/SOFT-O-PadP$1)") (class "Default")
      (node (ref "HARD/SOFT") (pin "P$1") (pinfunction "O_P$1") (pintype "passive"))
    )
    (net (code "77") (name "unconnected-(IC2B-OUT-Pad7)") (class "Default")
      (node (ref "IC2") (pin "7") (pinfunction "OUT_7") (pintype "output"))
    )
    (net (code "78") (name "unconnected-(SC_SW-S-PadP$3)") (class "Default")
      (node (ref "SC_SW") (pin "P$3") (pinfunction "S_P$3") (pintype "passive"))
    )
    (net (code "79") (name "unconnected-(VARIABLE/AUTO-S-PadP$3)") (class "Default")
      (node (ref "VARIABLE/AUTO") (pin "P$3") (pinfunction "S_P$3") (pintype "passive"))
    )
  )
)
